# power.net
KiCad netlist of a schematic drawn in EAGLE
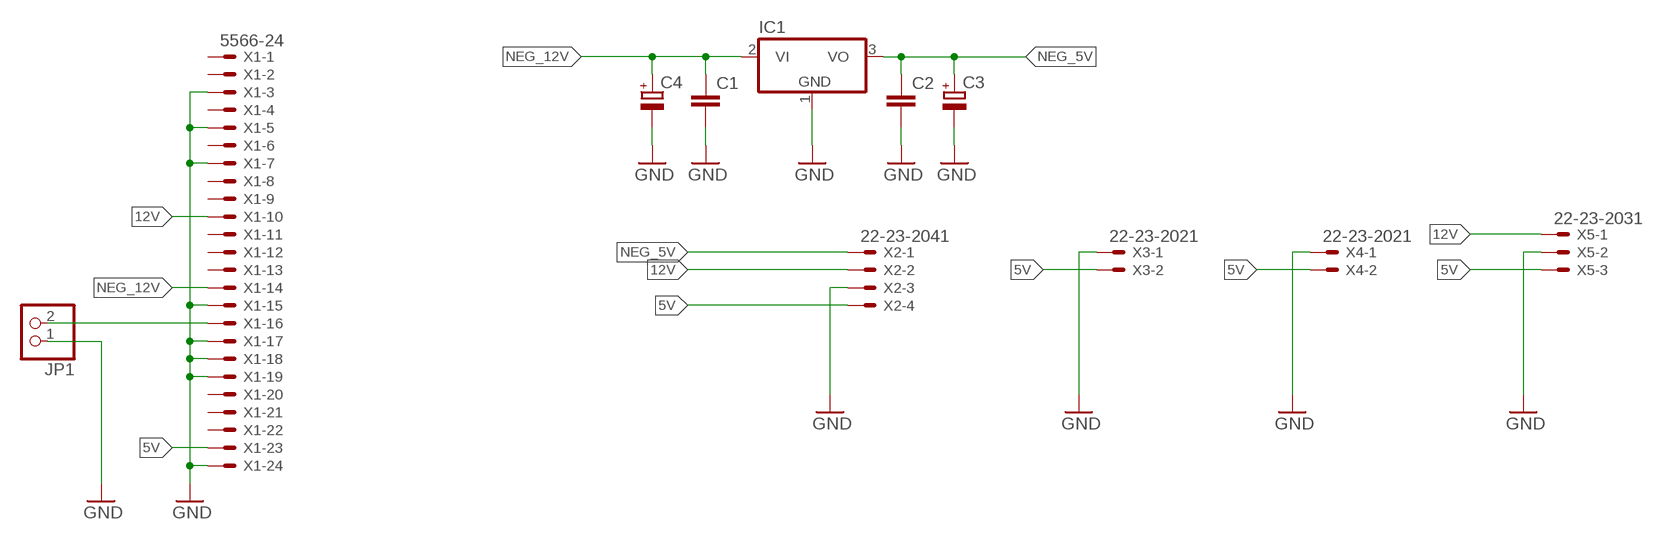
[diagram p0: schematic, sheet 1]

(export (version "E")
  (design (tool "Eeschema 10.0.6"))
  (components
    (comp (ref "C1")
      (value "C-EUC1206")
      (footprint "eagle-import:C1206")
      (libsource (lib "eagle-import") (part "C-EUC1206"))
    )
    (comp (ref "C2")
      (value "C-EUC1206")
      (footprint "eagle-import:C1206")
      (libsource (lib "eagle-import") (part "C-EUC1206"))
    )
    (comp (ref "C3")
      (value "CPOL-EUSMCB")
      (footprint "eagle-import:SMC_B")
      (libsource (lib "eagle-import") (part "CPOL-EUSMCB"))
    )
    (comp (ref "C4")
      (value "CPOL-EUSMCB")
      (footprint "eagle-import:SMC_B")
      (libsource (lib "eagle-import") (part "CPOL-EUSMCB"))
    )
    (comp (ref "IC1")
      (value "7905T")
      (footprint "eagle-import:TO220H")
      (libsource (lib "eagle-import") (part "79T05"))
    )
    (comp (ref "JP1")
      (value "PINHD-1X2")
      (footprint "eagle-import:1X02")
      (libsource (lib "eagle-import") (part "PINHD-1X2"))
    )
    (comp (ref "X1")
      (value "5566-24")
      (footprint "eagle-import:5566-24")
      (libsource (lib "eagle-import") (part "5566-24"))
    )
    (comp (ref "X2")
      (value "22-23-2041")
      (footprint "eagle-import:22-23-2041")
      (fields (field (name "MF") "MOLEX"))
      (libsource (lib "eagle-import") (part "22-23-2041"))
    )
    (comp (ref "X3")
      (value "22-23-2021")
      (footprint "eagle-import:22-23-2021")
      (fields (field (name "MF") "MOLEX"))
      (libsource (lib "eagle-import") (part "22-23-2021"))
    )
    (comp (ref "X4")
      (value "22-23-2021")
      (footprint "eagle-import:22-23-2021")
      (fields (field (name "MF") "MOLEX"))
      (libsource (lib "eagle-import") (part "22-23-2021"))
    )
    (comp (ref "X5")
      (value "22-23-2031")
      (footprint "eagle-import:22-23-2031")
      (fields (field (name "MF") "MOLEX"))
      (libsource (lib "eagle-import") (part "22-23-2031"))
    )
  )
  (nets
    (net (code "1") (name "5V") (class "Default")
      (node (ref "X1") (pin "23") (pinfunction "S_23") (pintype "passive"))
      (node (ref "X2") (pin "4") (pinfunction "S_4") (pintype "passive"))
      (node (ref "X3") (pin "2") (pinfunction "S_2") (pintype "passive"))
      (node (ref "X4") (pin "2") (pinfunction "S_2") (pintype "passive"))
      (node (ref "X5") (pin "3") (pinfunction "S_3") (pintype "passive"))
    )
    (net (code "2") (name "12V") (class "Default")
      (node (ref "X1") (pin "10") (pinfunction "S_10") (pintype "passive"))
      (node (ref "X2") (pin "2") (pinfunction "S_2") (pintype "passive"))
      (node (ref "X5") (pin "1") (pinfunction "S_1") (pintype "passive"))
    )
    (net (code "3") (name "GND") (class "Default")
      (node (ref "C1") (pin "2") (pinfunction "2_2") (pintype "passive"))
      (node (ref "C2") (pin "2") (pinfunction "2_2") (pintype "passive"))
      (node (ref "C3") (pin "-") (pinfunction "-_-") (pintype "passive"))
      (node (ref "C4") (pin "-") (pinfunction "-_-") (pintype "passive"))
      (node (ref "IC1") (pin "1") (pinfunction "GND_1") (pintype "passive"))
      (node (ref "JP1") (pin "1") (pinfunction "1_1") (pintype "passive"))
      (node (ref "X1") (pin "15") (pinfunction "S_15") (pintype "passive"))
      (node (ref "X1") (pin "17") (pinfunction "S_17") (pintype "passive"))
      (node (ref "X1") (pin "18") (pinfunction "S_18") (pintype "passive"))
      (node (ref "X1") (pin "19") (pinfunction "S_19") (pintype "passive"))
      (node (ref "X1") (pin "24") (pinfunction "S_24") (pintype "passive"))
      (node (ref "X1") (pin "3") (pinfunction "S_3") (pintype "passive"))
      (node (ref "X1") (pin "5") (pinfunction "S_5") (pintype "passive"))
      (node (ref "X1") (pin "7") (pinfunction "S_7") (pintype "passive"))
      (node (ref "X2") (pin "3") (pinfunction "S_3") (pintype "passive"))
      (node (ref "X3") (pin "1") (pinfunction "S_1") (pintype "passive"))
      (node (ref "X4") (pin "1") (pinfunction "S_1") (pintype "passive"))
      (node (ref "X5") (pin "2") (pinfunction "S_2") (pintype "passive"))
    )
    (net (code "4") (name "NEG_5V") (class "Default")
      (node (ref "C2") (pin "1") (pinfunction "1_1") (pintype "passive"))
      (node (ref "C3") (pin "+") (pinfunction "+_+") (pintype "passive"))
      (node (ref "IC1") (pin "3") (pinfunction "VO_3") (pintype "passive"))
      (node (ref "X2") (pin "1") (pinfunction "S_1") (pintype "passive"))
    )
    (net (code "5") (name "NEG_12V") (class "Default")
      (node (ref "C1") (pin "1") (pinfunction "1_1") (pintype "passive"))
      (node (ref "C4") (pin "+") (pinfunction "+_+") (pintype "passive"))
      (node (ref "IC1") (pin "2") (pinfunction "VI_2") (pintype "input"))
      (node (ref "X1") (pin "14") (pinfunction "S_14") (pintype "passive"))
    )
    (net (code "6") (name "Net-(X1H-S)") (class "Default")
      (node (ref "JP1") (pin "2") (pinfunction "2_2") (pintype "passive"))
      (node (ref "X1") (pin "16") (pinfunction "S_16") (pintype "passive"))
    )
    (net (code "7") (name "unconnected-(X1A-S-Pad1)") (class "Default")
      (node (ref "X1") (pin "1") (pinfunction "S_1") (pintype "passive"))
    )
    (net (code "8") (name "unconnected-(X1C-S-Pad11)") (class "Default")
      (node (ref "X1") (pin "11") (pinfunction "S_11") (pintype "passive"))
    )
    (net (code "9") (name "unconnected-(X1D-S-Pad12)") (class "Default")
      (node (ref "X1") (pin "12") (pinfunction "S_12") (pintype "passive"))
    )
    (net (code "10") (name "unconnected-(X1E-S-Pad13)") (class "Default")
      (node (ref "X1") (pin "13") (pinfunction "S_13") (pintype "passive"))
    )
    (net (code "11") (name "unconnected-(X1L-S-Pad2)") (class "Default")
      (node (ref "X1") (pin "2") (pinfunction "S_2") (pintype "passive"))
    )
    (net (code "12") (name "unconnected-(X1M-S-Pad20)") (class "Default")
      (node (ref "X1") (pin "20") (pinfunction "S_20") (pintype "passive"))
    )
    (net (code "13") (name "unconnected-(X1N-S-Pad21)") (class "Default")
      (node (ref "X1") (pin "21") (pinfunction "S_21") (pintype "passive"))
    )
    (net (code "14") (name "unconnected-(X1O-S-Pad22)") (class "Default")
      (node (ref "X1") (pin "22") (pinfunction "S_22") (pintype "passive"))
    )
    (net (code "15") (name "unconnected-(X1S-S-Pad4)") (class "Default")
      (node (ref "X1") (pin "4") (pinfunction "S_4") (pintype "passive"))
    )
    (net (code "16") (name "unconnected-(X1U-S-Pad6)") (class "Default")
      (node (ref "X1") (pin "6") (pinfunction "S_6") (pintype "passive"))
    )
    (net (code "17") (name "unconnected-(X1W-S-Pad8)") (class "Default")
      (node (ref "X1") (pin "8") (pinfunction "S_8") (pintype "passive"))
    )
    (net (code "18") (name "unconnected-(X1X-S-Pad9)") (class "Default")
      (node (ref "X1") (pin "9") (pinfunction "S_9") (pintype "passive"))
    )
  )
)
